# Copperclad_CooperBuffer_Amp_V0-5.net
KiCad netlist of a schematic drawn in EAGLE
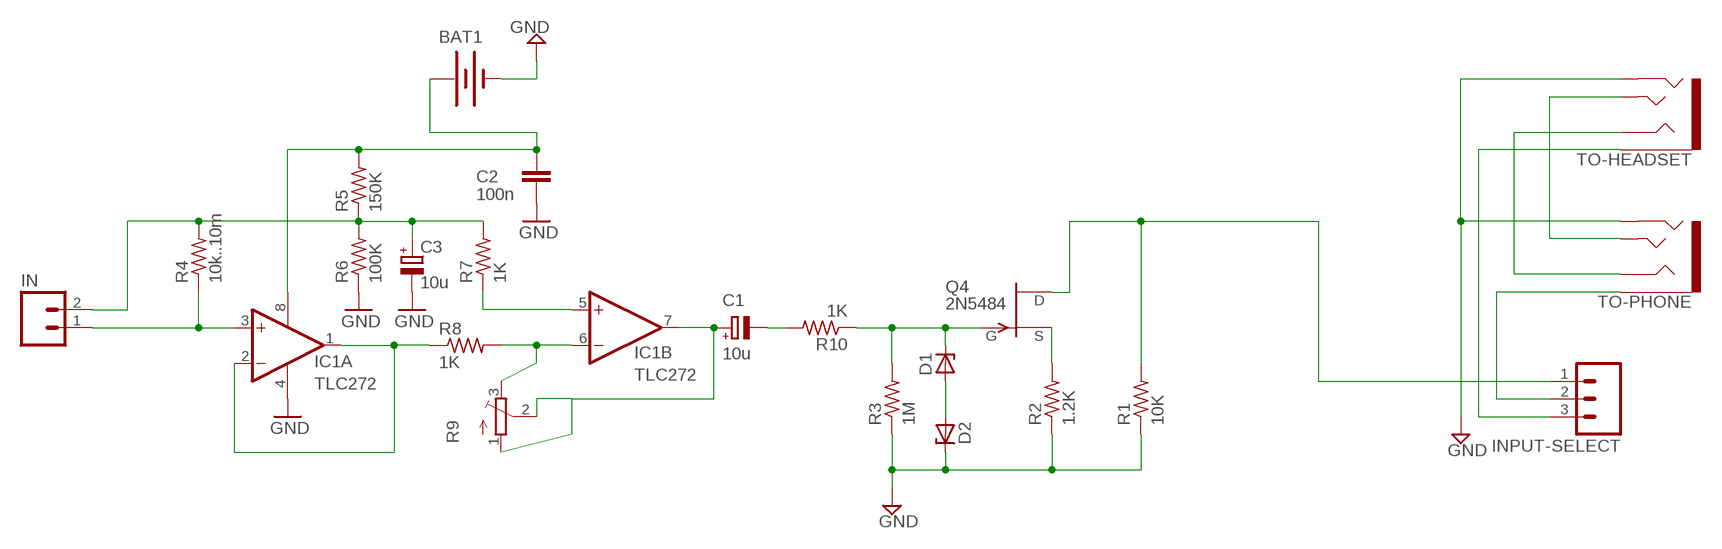
[diagram p0: schematic, sheet 1]

(export (version "E")
  (design (tool "Eeschema 10.0.6"))
  (components
    (comp (ref "BAT1")
      (value "BATTERYA23")
      (footprint "eagle-import:BATTERY-A23")
      (libsource (lib "eagle-import") (part "BATTERYA23"))
    )
    (comp (ref "C1")
      (value "10u")
      (footprint "eagle-import:E2,5-5")
      (libsource (lib "eagle-import") (part "CPOL-EUE2.5-5"))
    )
    (comp (ref "C2")
      (value "100n")
      (footprint "eagle-import:C025-025X050")
      (libsource (lib "eagle-import") (part "C-EU025-025X050"))
    )
    (comp (ref "C3")
      (value "10u")
      (footprint "eagle-import:E2,5-5")
      (libsource (lib "eagle-import") (part "CPOL-EUE2.5-5"))
    )
    (comp (ref "D1")
      (value "1N821")
      (footprint "eagle-import:DO35Z10")
      (libsource (lib "eagle-import") (part "1N821"))
    )
    (comp (ref "D2")
      (value "1N821")
      (footprint "eagle-import:DO35Z10")
      (libsource (lib "eagle-import") (part "1N821"))
    )
    (comp (ref "IC1")
      (value "TLC272")
      (footprint "eagle-import:DIL08")
      (libsource (lib "eagle-import") (part "TLC272P"))
    )
    (comp (ref "IN")
      (value "M02LOCK")
      (footprint "eagle-import:1X02_LOCK")
      (libsource (lib "eagle-import") (part "M02LOCK"))
    )
    (comp (ref "INPUT-SELECT")
      (value "M03LOCK")
      (footprint "eagle-import:1X03_LOCK")
      (libsource (lib "eagle-import") (part "M03LOCK"))
    )
    (comp (ref "Q4")
      (value "2N5484")
      (footprint "eagle-import:TO92-")
      (libsource (lib "eagle-import") (part "?5482N4"))
    )
    (comp (ref "R1")
      (value "10K")
      (footprint "eagle-import:0204V")
      (libsource (lib "eagle-import") (part "R-US_0204/2V"))
    )
    (comp (ref "R2")
      (value "1.2K")
      (footprint "eagle-import:0204V")
      (libsource (lib "eagle-import") (part "R-US_0204/2V"))
    )
    (comp (ref "R3")
      (value "1M")
      (footprint "eagle-import:0204V")
      (libsource (lib "eagle-import") (part "R-US_0204/2V"))
    )
    (comp (ref "R4")
      (value "10k..10m")
      (footprint "eagle-import:0204V")
      (libsource (lib "eagle-import") (part "R-US_0204/2V"))
    )
    (comp (ref "R5")
      (value "150K")
      (footprint "eagle-import:0204V")
      (libsource (lib "eagle-import") (part "R-US_0204/2V"))
    )
    (comp (ref "R6")
      (value "100K")
      (footprint "eagle-import:0204V")
      (libsource (lib "eagle-import") (part "R-US_0204/2V"))
    )
    (comp (ref "R7")
      (value "1K")
      (footprint "eagle-import:0204V")
      (libsource (lib "eagle-import") (part "R-US_0204/2V"))
    )
    (comp (ref "R8")
      (value "1K")
      (footprint "eagle-import:0204V")
      (libsource (lib "eagle-import") (part "R-US_0204/2V"))
    )
    (comp (ref "R9")
      (value "TRIMPOT3386")
      (footprint "eagle-import:TRIM-3386")
      (libsource (lib "eagle-import") (part "TRIMPOT3386"))
    )
    (comp (ref "R10")
      (value "1K")
      (footprint "eagle-import:0204V")
      (libsource (lib "eagle-import") (part "R-US_0204/2V"))
    )
    (comp (ref "TO-HEADSET")
      (value "AUDIO-JACK3")
      (footprint "eagle-import:AUDIO-JACK-TRRS-SMD")
      (libsource (lib "eagle-import") (part "AUDIO-JACK3"))
    )
    (comp (ref "TO-PHONE")
      (value "AUDIO-JACK3")
      (footprint "eagle-import:AUDIO-JACK-TRRS-SMD")
      (libsource (lib "eagle-import") (part "AUDIO-JACK3"))
    )
  )
  (nets
    (net (code "1") (name "GND") (class "Default")
      (node (ref "BAT1") (pin "GND@1") (pinfunction "-_GND@1") (pintype "power_in"))
      (node (ref "C2") (pin "1") (pinfunction "1_1") (pintype "passive"))
      (node (ref "C3") (pin "-") (pinfunction "-_-") (pintype "passive"))
      (node (ref "D2") (pin "C") (pinfunction "C_C") (pintype "passive"))
      (node (ref "IC1") (pin "4") (pinfunction "V-_4") (pintype "power_in"))
      (node (ref "R1") (pin "1") (pinfunction "1_1") (pintype "passive"))
      (node (ref "R2") (pin "1") (pinfunction "1_1") (pintype "passive"))
      (node (ref "R3") (pin "1") (pinfunction "1_1") (pintype "passive"))
      (node (ref "R6") (pin "1") (pinfunction "1_1") (pintype "passive"))
      (node (ref "TO-HEADSET") (pin "RING2") (pinfunction "RING2_RING2") (pintype "bidirectional"))
      (node (ref "TO-PHONE") (pin "RING2") (pinfunction "RING2_RING2") (pintype "bidirectional"))
    )
    (net (code "2") (name "Net-(BAT1-+)") (class "Default")
      (node (ref "BAT1") (pin "PWR@1") (pinfunction "+_PWR@1") (pintype "power_in"))
      (node (ref "C2") (pin "2") (pinfunction "2_2") (pintype "passive"))
      (node (ref "IC1") (pin "8") (pinfunction "V+_8") (pintype "power_in"))
      (node (ref "R5") (pin "2") (pinfunction "2_2") (pintype "passive"))
    )
    (net (code "3") (name "Net-(C1-Pad-)") (class "Default")
      (node (ref "C1") (pin "-") (pinfunction "-_-") (pintype "passive"))
      (node (ref "R10") (pin "2") (pinfunction "2_2") (pintype "passive"))
    )
    (net (code "4") (name "Net-(C3-Pad+)") (class "Default")
      (node (ref "C3") (pin "+") (pinfunction "+_+") (pintype "passive"))
      (node (ref "IN") (pin "2") (pinfunction "2_2") (pintype "passive"))
      (node (ref "R4") (pin "2") (pinfunction "2_2") (pintype "passive"))
      (node (ref "R5") (pin "1") (pinfunction "1_1") (pintype "passive"))
      (node (ref "R6") (pin "2") (pinfunction "2_2") (pintype "passive"))
      (node (ref "R7") (pin "2") (pinfunction "2_2") (pintype "passive"))
    )
    (net (code "5") (name "Net-(D1-PadA)") (class "Default")
      (node (ref "D1") (pin "A") (pinfunction "A_A") (pintype "passive"))
      (node (ref "D2") (pin "A") (pinfunction "A_A") (pintype "passive"))
    )
    (net (code "6") (name "Net-(IC1A-+IN)") (class "Default")
      (node (ref "IC1") (pin "3") (pinfunction "+IN_3") (pintype "input"))
      (node (ref "IN") (pin "1") (pinfunction "1_1") (pintype "passive"))
      (node (ref "R4") (pin "1") (pinfunction "1_1") (pintype "passive"))
    )
    (net (code "7") (name "Net-(IC1A--IN)") (class "Default")
      (node (ref "IC1") (pin "1") (pinfunction "OUT_1") (pintype "output"))
      (node (ref "IC1") (pin "2") (pinfunction "-IN_2") (pintype "input"))
      (node (ref "R8") (pin "1") (pinfunction "1_1") (pintype "passive"))
    )
    (net (code "8") (name "Net-(IC1B-+IN)") (class "Default")
      (node (ref "IC1") (pin "5") (pinfunction "+IN_5") (pintype "input"))
      (node (ref "R7") (pin "1") (pinfunction "1_1") (pintype "passive"))
    )
    (net (code "9") (name "Net-(IC1B--IN)") (class "Default")
      (node (ref "IC1") (pin "6") (pinfunction "-IN_6") (pintype "input"))
      (node (ref "R8") (pin "2") (pinfunction "2_2") (pintype "passive"))
      (node (ref "R9") (pin "3") (pinfunction "E_3") (pintype "passive"))
    )
    (net (code "10") (name "Net-(IC1B-OUT)") (class "Default")
      (node (ref "C1") (pin "+") (pinfunction "+_+") (pintype "passive"))
      (node (ref "IC1") (pin "7") (pinfunction "OUT_7") (pintype "output"))
      (node (ref "R9") (pin "1") (pinfunction "A_1") (pintype "passive"))
      (node (ref "R9") (pin "2") (pinfunction "S_2") (pintype "passive"))
    )
    (net (code "11") (name "Net-(INPUT-SELECT-Pad2)") (class "Default")
      (node (ref "INPUT-SELECT") (pin "2") (pinfunction "2_2") (pintype "passive"))
      (node (ref "TO-PHONE") (pin "EARTH") (pinfunction "EARTH_EARTH") (pintype "bidirectional"))
    )
    (net (code "12") (name "Net-(INPUT-SELECT-Pad3)") (class "Default")
      (node (ref "INPUT-SELECT") (pin "3") (pinfunction "3_3") (pintype "passive"))
      (node (ref "TO-HEADSET") (pin "EARTH") (pinfunction "EARTH_EARTH") (pintype "bidirectional"))
    )
    (net (code "13") (name "Net-(Q4-D)") (class "Default")
      (node (ref "INPUT-SELECT") (pin "1") (pinfunction "1_1") (pintype "passive"))
      (node (ref "Q4") (pin "3") (pinfunction "D_3") (pintype "passive"))
      (node (ref "R1") (pin "2") (pinfunction "2_2") (pintype "passive"))
    )
    (net (code "14") (name "Net-(Q4-G)") (class "Default")
      (node (ref "D1") (pin "C") (pinfunction "C_C") (pintype "passive"))
      (node (ref "Q4") (pin "1") (pinfunction "G_1") (pintype "passive"))
      (node (ref "R10") (pin "1") (pinfunction "1_1") (pintype "passive"))
      (node (ref "R3") (pin "2") (pinfunction "2_2") (pintype "passive"))
    )
    (net (code "15") (name "Net-(Q4-S)") (class "Default")
      (node (ref "Q4") (pin "2") (pinfunction "S_2") (pintype "passive"))
      (node (ref "R2") (pin "2") (pinfunction "2_2") (pintype "passive"))
    )
    (net (code "16") (name "Net-(TO-HEADSET-PadRING1)") (class "Default")
      (node (ref "TO-HEADSET") (pin "RING1") (pinfunction "RING1_RING1") (pintype "bidirectional"))
      (node (ref "TO-PHONE") (pin "RING1") (pinfunction "RING1_RING1") (pintype "bidirectional"))
    )
    (net (code "17") (name "Net-(TO-HEADSET-PadTIP)") (class "Default")
      (node (ref "TO-HEADSET") (pin "TIP") (pinfunction "TIP_TIP") (pintype "bidirectional"))
      (node (ref "TO-PHONE") (pin "TIP") (pinfunction "TIP_TIP") (pintype "bidirectional"))
    )
  )
)
